# Terminierung_RS485_RJ45_Pads_V04.net
KiCad netlist of a schematic drawn in EAGLE
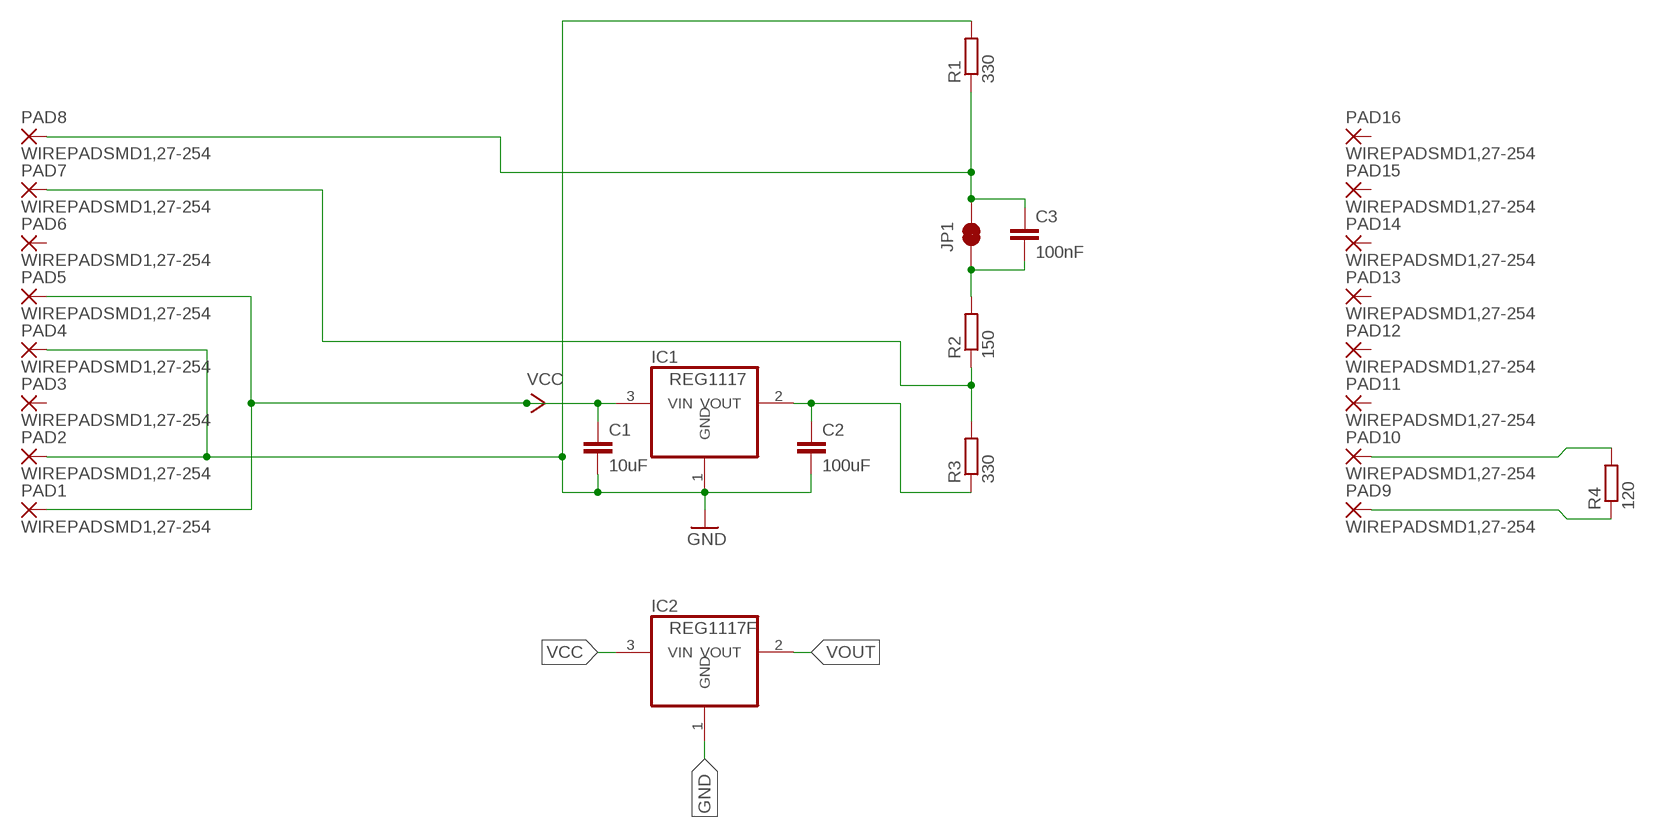
[diagram p0: schematic, sheet 1]

(export (version "E")
  (design (tool "Eeschema 10.0.6"))
  (components
    (comp (ref "C1")
      (value "10uF")
      (footprint "eagle-import:C0805K")
      (libsource (lib "eagle-import") (part "C-EUC0805K"))
    )
    (comp (ref "C2")
      (value "100uF")
      (footprint "eagle-import:C1210")
      (libsource (lib "eagle-import") (part "C-EUC1210"))
    )
    (comp (ref "C3")
      (value "100nF")
      (footprint "eagle-import:C0805K")
      (libsource (lib "eagle-import") (part "C-EUC0805K"))
    )
    (comp (ref "IC1")
      (value "REG1117")
      (footprint "eagle-import:SOT223")
      (libsource (lib "eagle-import") (part "REG1117"))
    )
    (comp (ref "IC2")
      (value "REG1117F")
      (footprint "eagle-import:DD-3")
      (fields (field (name "MF") "TEXAS INSTRUMENTS") (field (name "MPN") "REG1117FAKTTT"))
      (libsource (lib "eagle-import") (part "REG1117F"))
    )
    (comp (ref "JP1")
      (value "JUMPER-SMT_2_NC_TRACE_SILK")
      (footprint "eagle-import:SMT-JUMPER_2_NC_TRACE_SILK")
      (libsource (lib "eagle-import") (part "JUMPER-SMT_2_NC_TRACE_SILK"))
    )
    (comp (ref "PAD1")
      (value "WIREPADSMD1,27-254")
      (footprint "eagle-import:SMD1,27-2,54")
      (libsource (lib "eagle-import") (part "WIREPADSMD1,27-254"))
    )
    (comp (ref "PAD2")
      (value "WIREPADSMD1,27-254")
      (footprint "eagle-import:SMD1,27-2,54")
      (libsource (lib "eagle-import") (part "WIREPADSMD1,27-254"))
    )
    (comp (ref "PAD3")
      (value "WIREPADSMD1,27-254")
      (footprint "eagle-import:SMD1,27-2,54")
      (libsource (lib "eagle-import") (part "WIREPADSMD1,27-254"))
    )
    (comp (ref "PAD4")
      (value "WIREPADSMD1,27-254")
      (footprint "eagle-import:SMD1,27-2,54")
      (libsource (lib "eagle-import") (part "WIREPADSMD1,27-254"))
    )
    (comp (ref "PAD5")
      (value "WIREPADSMD1,27-254")
      (footprint "eagle-import:SMD1,27-2,54")
      (libsource (lib "eagle-import") (part "WIREPADSMD1,27-254"))
    )
    (comp (ref "PAD6")
      (value "WIREPADSMD1,27-254")
      (footprint "eagle-import:SMD1,27-2,54")
      (libsource (lib "eagle-import") (part "WIREPADSMD1,27-254"))
    )
    (comp (ref "PAD7")
      (value "WIREPADSMD1,27-254")
      (footprint "eagle-import:SMD1,27-2,54")
      (libsource (lib "eagle-import") (part "WIREPADSMD1,27-254"))
    )
    (comp (ref "PAD8")
      (value "WIREPADSMD1,27-254")
      (footprint "eagle-import:SMD1,27-2,54")
      (libsource (lib "eagle-import") (part "WIREPADSMD1,27-254"))
    )
    (comp (ref "PAD9")
      (value "WIREPADSMD1,27-254")
      (footprint "eagle-import:SMD1,27-2,54")
      (libsource (lib "eagle-import") (part "WIREPADSMD1,27-254"))
    )
    (comp (ref "PAD10")
      (value "WIREPADSMD1,27-254")
      (footprint "eagle-import:SMD1,27-2,54")
      (libsource (lib "eagle-import") (part "WIREPADSMD1,27-254"))
    )
    (comp (ref "PAD11")
      (value "WIREPADSMD1,27-254")
      (footprint "eagle-import:SMD1,27-2,54")
      (libsource (lib "eagle-import") (part "WIREPADSMD1,27-254"))
    )
    (comp (ref "PAD12")
      (value "WIREPADSMD1,27-254")
      (footprint "eagle-import:SMD1,27-2,54")
      (libsource (lib "eagle-import") (part "WIREPADSMD1,27-254"))
    )
    (comp (ref "PAD13")
      (value "WIREPADSMD1,27-254")
      (footprint "eagle-import:SMD1,27-2,54")
      (libsource (lib "eagle-import") (part "WIREPADSMD1,27-254"))
    )
    (comp (ref "PAD14")
      (value "WIREPADSMD1,27-254")
      (footprint "eagle-import:SMD1,27-2,54")
      (libsource (lib "eagle-import") (part "WIREPADSMD1,27-254"))
    )
    (comp (ref "PAD15")
      (value "WIREPADSMD1,27-254")
      (footprint "eagle-import:SMD1,27-2,54")
      (libsource (lib "eagle-import") (part "WIREPADSMD1,27-254"))
    )
    (comp (ref "PAD16")
      (value "WIREPADSMD1,27-254")
      (footprint "eagle-import:SMD1,27-2,54")
      (libsource (lib "eagle-import") (part "WIREPADSMD1,27-254"))
    )
    (comp (ref "R1")
      (value "330")
      (footprint "eagle-import:R0805")
      (libsource (lib "eagle-import") (part "R-EU_R0805"))
    )
    (comp (ref "R2")
      (value "150")
      (footprint "eagle-import:R0805")
      (libsource (lib "eagle-import") (part "R-EU_R0805"))
    )
    (comp (ref "R3")
      (value "330")
      (footprint "eagle-import:R0805")
      (libsource (lib "eagle-import") (part "R-EU_R0805"))
    )
    (comp (ref "R4")
      (value "120")
      (footprint "eagle-import:R0805")
      (libsource (lib "eagle-import") (part "R-EU_R0805"))
    )
  )
  (nets
    (net (code "1") (name "GND") (class "Default")
      (node (ref "C1") (pin "2") (pinfunction "2_2") (pintype "passive"))
      (node (ref "C2") (pin "2") (pinfunction "2_2") (pintype "passive"))
      (node (ref "IC1") (pin "1") (pinfunction "GND_1") (pintype "power_in"))
      (node (ref "IC2") (pin "1") (pinfunction "GND_1") (pintype "power_in"))
      (node (ref "PAD2") (pin "1") (pinfunction "P_1") (pintype "passive"))
      (node (ref "PAD4") (pin "1") (pinfunction "P_1") (pintype "passive"))
      (node (ref "R1") (pin "2") (pinfunction "2_2") (pintype "passive"))
    )
    (net (code "2") (name "Net-(C3-Pad2)") (class "Default")
      (node (ref "C3") (pin "2") (pinfunction "2_2") (pintype "passive"))
      (node (ref "JP1") (pin "1") (pinfunction "1_1") (pintype "passive"))
      (node (ref "R2") (pin "2") (pinfunction "2_2") (pintype "passive"))
    )
    (net (code "3") (name "Net-(PAD7-P)") (class "Default")
      (node (ref "PAD7") (pin "1") (pinfunction "P_1") (pintype "passive"))
      (node (ref "R2") (pin "1") (pinfunction "1_1") (pintype "passive"))
      (node (ref "R3") (pin "2") (pinfunction "2_2") (pintype "passive"))
    )
    (net (code "4") (name "Net-(PAD8-P)") (class "Default")
      (node (ref "C3") (pin "1") (pinfunction "1_1") (pintype "passive"))
      (node (ref "JP1") (pin "2") (pinfunction "2_2") (pintype "passive"))
      (node (ref "PAD8") (pin "1") (pinfunction "P_1") (pintype "passive"))
      (node (ref "R1") (pin "1") (pinfunction "1_1") (pintype "passive"))
    )
    (net (code "5") (name "Net-(PAD9-P)") (class "Default")
      (node (ref "PAD9") (pin "1") (pinfunction "P_1") (pintype "passive"))
      (node (ref "R4") (pin "1") (pinfunction "1_1") (pintype "passive"))
    )
    (net (code "6") (name "Net-(PAD10-P)") (class "Default")
      (node (ref "PAD10") (pin "1") (pinfunction "P_1") (pintype "passive"))
      (node (ref "R4") (pin "2") (pinfunction "2_2") (pintype "passive"))
    )
    (net (code "7") (name "VCC") (class "Default")
      (node (ref "C1") (pin "1") (pinfunction "1_1") (pintype "passive"))
      (node (ref "IC1") (pin "3") (pinfunction "VIN_3") (pintype "input"))
      (node (ref "IC2") (pin "3") (pinfunction "VIN_3") (pintype "input"))
      (node (ref "PAD1") (pin "1") (pinfunction "P_1") (pintype "passive"))
      (node (ref "PAD5") (pin "1") (pinfunction "P_1") (pintype "passive"))
    )
    (net (code "8") (name "VOUT") (class "Default")
      (node (ref "C2") (pin "1") (pinfunction "1_1") (pintype "passive"))
      (node (ref "IC1") (pin "2") (pinfunction "VOUT_2") (pintype "output"))
      (node (ref "IC2") (pin "2") (pinfunction "VOUT_2") (pintype "output"))
      (node (ref "R3") (pin "1") (pinfunction "1_1") (pintype "passive"))
    )
    (net (code "9") (name "unconnected-(PAD3-P-Pad1)") (class "Default")
      (node (ref "PAD3") (pin "1") (pinfunction "P_1") (pintype "passive"))
    )
    (net (code "10") (name "unconnected-(PAD6-P-Pad1)") (class "Default")
      (node (ref "PAD6") (pin "1") (pinfunction "P_1") (pintype "passive"))
    )
    (net (code "11") (name "unconnected-(PAD11-P-Pad1)") (class "Default")
      (node (ref "PAD11") (pin "1") (pinfunction "P_1") (pintype "passive"))
    )
    (net (code "12") (name "unconnected-(PAD12-P-Pad1)") (class "Default")
      (node (ref "PAD12") (pin "1") (pinfunction "P_1") (pintype "passive"))
    )
    (net (code "13") (name "unconnected-(PAD13-P-Pad1)") (class "Default")
      (node (ref "PAD13") (pin "1") (pinfunction "P_1") (pintype "passive"))
    )
    (net (code "14") (name "unconnected-(PAD14-P-Pad1)") (class "Default")
      (node (ref "PAD14") (pin "1") (pinfunction "P_1") (pintype "passive"))
    )
    (net (code "15") (name "unconnected-(PAD15-P-Pad1)") (class "Default")
      (node (ref "PAD15") (pin "1") (pinfunction "P_1") (pintype "passive"))
    )
    (net (code "16") (name "unconnected-(PAD16-P-Pad1)") (class "Default")
      (node (ref "PAD16") (pin "1") (pinfunction "P_1") (pintype "passive"))
    )
  )
)
